# YaskawaSpeedControl_fix.net
KiCad netlist of a schematic drawn in EAGLE
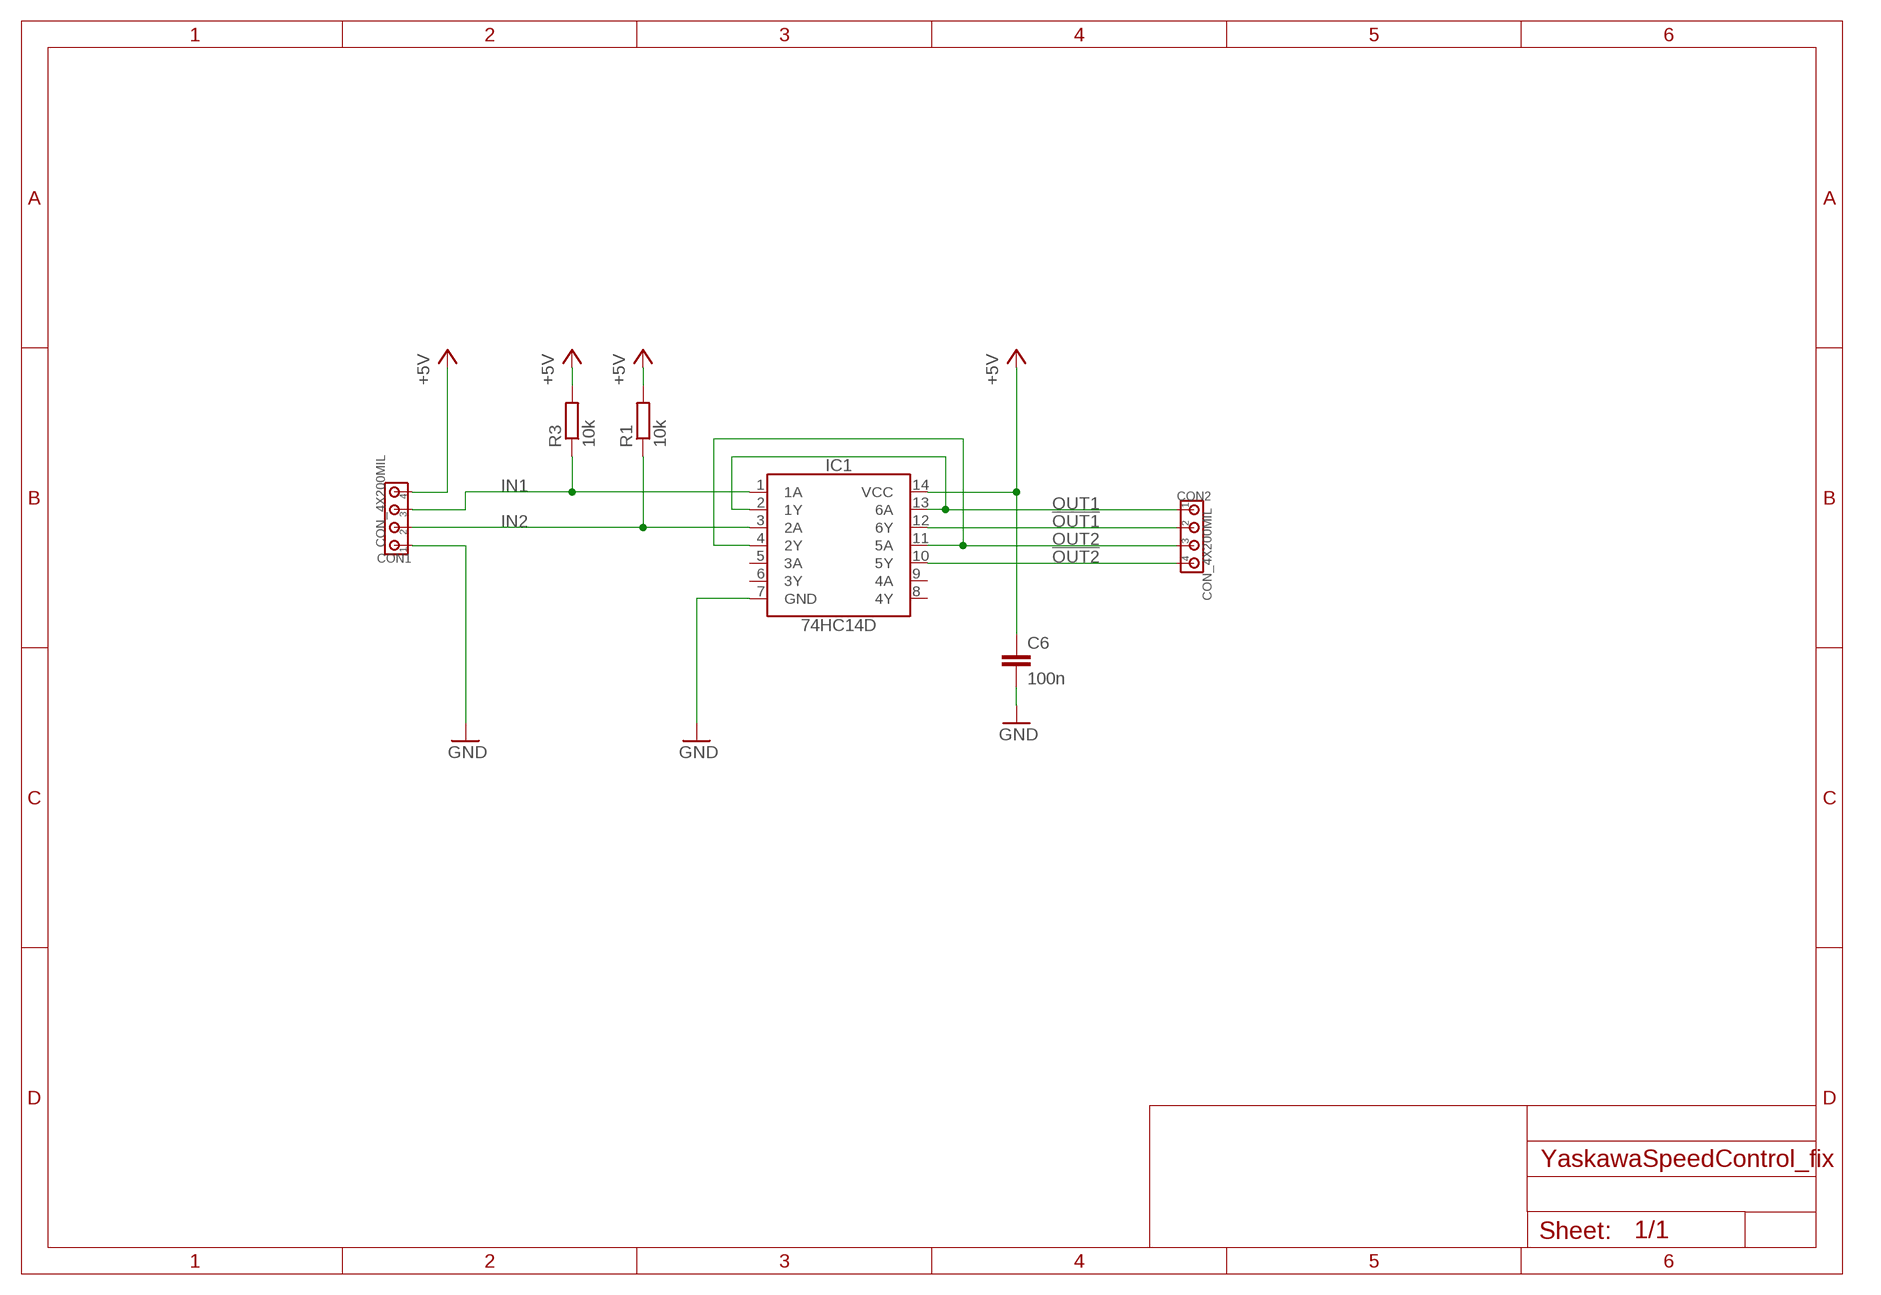
[diagram p0: schematic, sheet 1]

(export (version "E")
  (design (tool "Eeschema 10.0.6"))
  (components
    (comp (ref "C6")
      (value "100n")
      (footprint "eagle-import:C0805")
      (libsource (lib "eagle-import") (part "CC0805"))
    )
    (comp (ref "CON1")
      (value "CON_4X200MIL")
      (footprint "eagle-import:200MIL_4X")
      (libsource (lib "eagle-import") (part "CON_4X200MIL"))
    )
    (comp (ref "CON2")
      (value "CON_4X200MIL")
      (footprint "eagle-import:200MIL_4X")
      (libsource (lib "eagle-import") (part "CON_4X200MIL"))
    )
    (comp (ref "IC1")
      (value "74HC14D")
      (footprint "eagle-import:SO14")
      (libsource (lib "eagle-import") (part "74HC14D"))
    )
    (comp (ref "R1")
      (value "10k")
      (footprint "eagle-import:R0805")
      (libsource (lib "eagle-import") (part "RESISTORR0805"))
    )
    (comp (ref "R3")
      (value "10k")
      (footprint "eagle-import:R0805")
      (libsource (lib "eagle-import") (part "RESISTORR0805"))
    )
  )
  (nets
    (net (code "1") (name "+5V") (class "Default")
      (node (ref "C6") (pin "1") (pinfunction "1_1") (pintype "passive"))
      (node (ref "CON1") (pin "4") (pinfunction "4_4") (pintype "passive"))
      (node (ref "IC1") (pin "14") (pinfunction "VCC_14") (pintype "power_in"))
      (node (ref "R1") (pin "2") (pinfunction "2_2") (pintype "passive"))
      (node (ref "R3") (pin "2") (pinfunction "2_2") (pintype "passive"))
    )
    (net (code "2") (name "/IN1") (class "Default")
      (node (ref "CON1") (pin "3") (pinfunction "3_3") (pintype "passive"))
      (node (ref "IC1") (pin "1") (pinfunction "1A_1") (pintype "input"))
      (node (ref "R3") (pin "1") (pinfunction "1_1") (pintype "passive"))
    )
    (net (code "3") (name "/IN2") (class "Default")
      (node (ref "CON1") (pin "2") (pinfunction "2_2") (pintype "passive"))
      (node (ref "IC1") (pin "3") (pinfunction "2A_3") (pintype "input"))
      (node (ref "R1") (pin "1") (pinfunction "1_1") (pintype "passive"))
    )
    (net (code "4") (name "/OUT1") (class "Default")
      (node (ref "CON2") (pin "1") (pinfunction "1_1") (pintype "passive"))
      (node (ref "IC1") (pin "13") (pinfunction "6A_13") (pintype "bidirectional"))
      (node (ref "IC1") (pin "2") (pinfunction "1Y_2") (pintype "input"))
    )
    (net (code "5") (name "/OUT2") (class "Default")
      (node (ref "CON2") (pin "3") (pinfunction "3_3") (pintype "passive"))
      (node (ref "IC1") (pin "11") (pinfunction "5A_11") (pintype "bidirectional"))
      (node (ref "IC1") (pin "4") (pinfunction "2Y_4") (pintype "input"))
    )
    (net (code "6") (name "/~{OUT1}") (class "Default")
      (node (ref "CON2") (pin "2") (pinfunction "2_2") (pintype "passive"))
      (node (ref "IC1") (pin "12") (pinfunction "6Y_12") (pintype "bidirectional"))
    )
    (net (code "7") (name "/~{OUT2}") (class "Default")
      (node (ref "CON2") (pin "4") (pinfunction "4_4") (pintype "passive"))
      (node (ref "IC1") (pin "10") (pinfunction "5Y_10") (pintype "bidirectional"))
    )
    (net (code "8") (name "GND") (class "Default")
      (node (ref "C6") (pin "2") (pinfunction "2_2") (pintype "passive"))
      (node (ref "CON1") (pin "1") (pinfunction "1_1") (pintype "passive"))
      (node (ref "IC1") (pin "7") (pinfunction "GND_7") (pintype "bidirectional"))
    )
    (net (code "9") (name "unconnected-(IC1-3A-Pad5)") (class "Default")
      (node (ref "IC1") (pin "5") (pinfunction "3A_5") (pintype "input"))
    )
    (net (code "10") (name "unconnected-(IC1-3Y-Pad6)") (class "Default")
      (node (ref "IC1") (pin "6") (pinfunction "3Y_6") (pintype "input"))
    )
    (net (code "11") (name "unconnected-(IC1-4A-Pad9)") (class "Default")
      (node (ref "IC1") (pin "9") (pinfunction "4A_9") (pintype "bidirectional"))
    )
    (net (code "12") (name "unconnected-(IC1-4Y-Pad8)") (class "Default")
      (node (ref "IC1") (pin "8") (pinfunction "4Y_8") (pintype "bidirectional"))
    )
  )
)
